# IO_PWR_FMU3_REV_C.net
KiCad netlist of a schematic drawn in Altium Designer
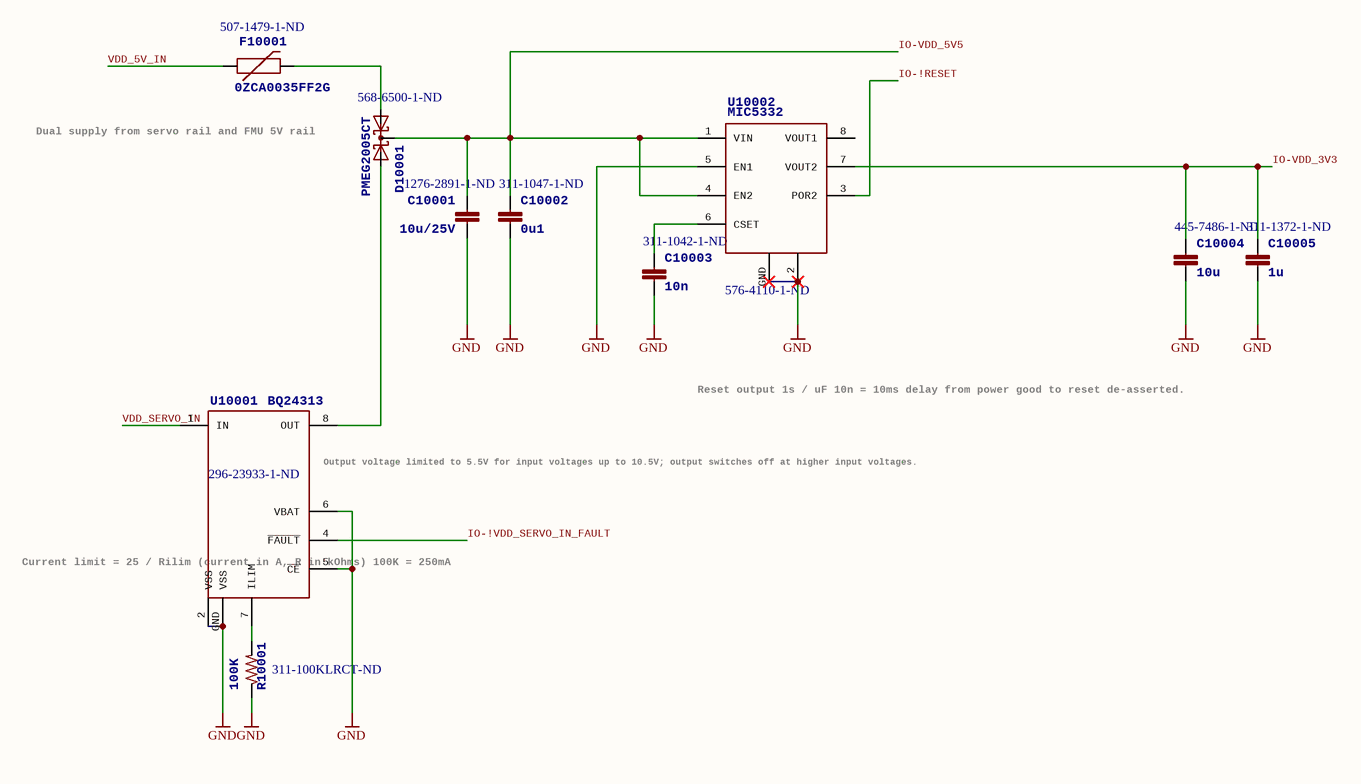
[diagram p0: IO_PWR_FMU3_REV_C.SchDoc]

(export (version "E")
  (design (tool "Eeschema 10.0.6"))
  (components
    (comp (ref "C10001")
      (value "10u/25V")
      (footprint "0805-CAP")
      (description "CAP CER 10UF 25V 10% X5R 0805")
      (fields
        (field (name "PARTNO") "CL21A106KAYNNNE")
        (field (name "SUPPLIER PART NUMBER 1") "1276-2891-1-ND")
        (field (name "3DR_PARTNO") "ECM0714")
      )
      (libsource (lib "pixhawk2") (part "CAP0805"))
    )
    (comp (ref "C10002")
      (value "0u1")
      (footprint "0402-CAP")
      (description "CAP CER 0.1UF 16V Y5V 0402")
      (fields
        (field (name "PARTNO") "CC0402ZRY5V7BB104")
        (field (name "SUPPLIER PART NUMBER 1") "311-1047-1-ND")
        (field (name "3DR_PARTNO") "ECM0700")
      )
      (libsource (lib "pixhawk2") (part "CAP0402"))
    )
    (comp (ref "C10003")
      (value "10n")
      (footprint "0402-CAP")
      (description "CAP CER 10000PF 16V 10% X7R 0402")
      (fields
        (field (name "PARTNO") "CC0402KRX7R7BB103")
        (field (name "SUPPLIER PART NUMBER 1") "311-1042-1-ND")
        (field (name "3DR_PARTNO") "ECM0711")
      )
      (libsource (lib "pixhawk2") (part "CAP0402"))
    )
    (comp (ref "C10004")
      (value "10u")
      (footprint "0603-CAP")
      (description "CAP CER 10UF 10V 10% X5R 0603")
      (fields
        (field (name "PARTNO") "C1608X5R1A106K080AC")
        (field (name "SUPPLIER PART NUMBER 1") "445-7486-1-ND")
        (field (name "3DR_PARTNO") "ECM0712")
      )
      (libsource (lib "pixhawk2") (part "CAP0603"))
    )
    (comp (ref "C10005")
      (value "1u")
      (footprint "0603-CAP")
      (description "CAP CER 1UF 16V Y5V 0603")
      (fields
        (field (name "PARTNO") "CC0603ZRY5V7BB105")
        (field (name "SUPPLIER PART NUMBER 1") "311-1372-1-ND")
        (field (name "3DR_PARTNO") "ECM0705")
      )
      (libsource (lib "pixhawk2") (part "CAP0603"))
    )
    (comp (ref "D10001")
      (value "PMEG2005CT")
      (footprint "SOT23-3")
      (description "DIODE SCHOTTKY 20V 500MA TO236AB")
      (fields (field (name "SUPPLIER PART NUMBER 1") "568-6500-1-ND") (field (name "3DR_PARTNO") "ECM0838"))
      (libsource (lib "pixhawk2") (part "PMEG2005CT"))
    )
    (comp (ref "F10001")
      (value "0ZCA0035FF2G")
      (footprint "PTC-1206")
      (description "PTC RESTTBLE 0.35A 16V CHIP 1206")
      (fields (field (name "SUPPLIER PART NUMBER 1") "507-1479-1-ND") (field (name "3DR_PARTNO") "ECM0802"))
      (libsource (lib "pixhawk2") (part "PTCSMD"))
    )
    (comp (ref "R10001")
      (value "100K")
      (footprint "0402-RES")
      (description "RES 100K OHM 1/16W 1% 0402 SMD")
      (fields
        (field (name "SUPPLIER PART NUMBER 1") "311-100KLRCT-ND")
        (field (name "3DR_PARTNO") "ECM0818")
        (field (name "PARTNO") "RC0402FR-07100KL")
      )
      (libsource (lib "pixhawk2") (part "RESISTOR0402-RES"))
    )
    (comp (ref "U10001")
      (value "BQ24313")
      (footprint "QFN8-DSG")
      (description "IC LI+ CHARGER FRONT END 8-SON")
      (fields
        (field (name "SUPPLIER PART NUMBER 1") "296-23933-1-ND")
        (field (name "3DR_PARTNO") "ECM0824")
        (field (name "PARTNO") "BQ24313DSGT")
      )
      (libsource (lib "pixhawk2") (part "BQ24313"))
    )
    (comp (ref "U10002")
      (value "MIC5332")
      (footprint "MLF-8-EPAD")
      (description "IC REG LDO 3.3V 0.3A 8TMLF")
      (fields
        (field (name "SUPPLIER PART NUMBER 1") "576-4110-1-ND")
        (field (name "3DR_PARTNO") "ECM0832")
        (field (name "PARTNO") "MIC5332-SSYMT TR")
      )
      (libsource (lib "pixhawk2") (part "MIC5332"))
    )
  )
  (nets
    (net (code "1") (name "/IO-!RESET") (class "Default")
      (node (ref "U10002") (pin "3") (pinfunction "POR2_3") (pintype "passive"))
    )
    (net (code "2") (name "/IO-!VDD_SERVO_IN_FAULT") (class "Default")
      (node (ref "U10001") (pin "4") (pinfunction "~{FAULT}_4") (pintype "passive"))
    )
    (net (code "3") (name "/IO-VDD_3V3") (class "Default")
      (node (ref "C10004") (pin "P$1") (pinfunction "1_P$1") (pintype "passive"))
      (node (ref "C10005") (pin "P$1") (pinfunction "1_P$1") (pintype "passive"))
      (node (ref "U10002") (pin "7") (pinfunction "VOUT2_7") (pintype "passive"))
    )
    (net (code "4") (name "/IO-VDD_5V5") (class "Default")
      (node (ref "C10001") (pin "P$1") (pinfunction "1_P$1") (pintype "passive"))
      (node (ref "C10002") (pin "P$1") (pinfunction "1_P$1") (pintype "passive"))
      (node (ref "D10001") (pin "3") (pinfunction "CC_3") (pintype "passive"))
      (node (ref "U10002") (pin "1") (pinfunction "VIN_1") (pintype "passive"))
      (node (ref "U10002") (pin "4") (pinfunction "EN2_4") (pintype "passive"))
    )
    (net (code "5") (name "/VDD_5V_IN") (class "Default")
      (node (ref "F10001") (pin "1") (pinfunction "1_1") (pintype "passive"))
    )
    (net (code "6") (name "/VDD_SERVO_IN") (class "Default")
      (node (ref "U10001") (pin "1") (pinfunction "IN_1") (pintype "passive"))
    )
    (net (code "7") (name "GND") (class "Default")
      (node (ref "C10001") (pin "P$2") (pinfunction "2_P$2") (pintype "passive"))
      (node (ref "C10002") (pin "P$2") (pinfunction "2_P$2") (pintype "passive"))
      (node (ref "C10003") (pin "P$2") (pinfunction "2_P$2") (pintype "passive"))
      (node (ref "C10004") (pin "P$2") (pinfunction "2_P$2") (pintype "passive"))
      (node (ref "C10005") (pin "P$2") (pinfunction "2_P$2") (pintype "passive"))
      (node (ref "R10001") (pin "P$1") (pinfunction "1_P$1") (pintype "passive"))
      (node (ref "U10001") (pin "2") (pinfunction "VSS_2") (pintype "passive"))
      (node (ref "U10001") (pin "5") (pinfunction "~{CE}_5") (pintype "passive"))
      (node (ref "U10001") (pin "6") (pinfunction "VBAT_6") (pintype "passive"))
      (node (ref "U10001") (pin "GND") (pinfunction "VSS_GND") (pintype "passive"))
      (node (ref "U10002") (pin "2") (pinfunction "GND_2") (pintype "power_in"))
      (node (ref "U10002") (pin "5") (pinfunction "EN1_5") (pintype "passive"))
      (node (ref "U10002") (pin "GND") (pinfunction "GND_GND") (pintype "power_in"))
    )
    (net (code "8") (name "Net-(C10003-1)") (class "Default")
      (node (ref "C10003") (pin "P$1") (pinfunction "1_P$1") (pintype "passive"))
      (node (ref "U10002") (pin "6") (pinfunction "CSET_6") (pintype "passive"))
    )
    (net (code "9") (name "Net-(D10001-A1)") (class "Default")
      (node (ref "D10001") (pin "1") (pinfunction "A1_1") (pintype "passive"))
      (node (ref "F10001") (pin "2") (pinfunction "2_2") (pintype "passive"))
    )
    (net (code "10") (name "Net-(D10001-A2)") (class "Default")
      (node (ref "D10001") (pin "2") (pinfunction "A2_2") (pintype "passive"))
      (node (ref "U10001") (pin "8") (pinfunction "OUT_8") (pintype "passive"))
    )
    (net (code "11") (name "Net-(R10001-2)") (class "Default")
      (node (ref "R10001") (pin "P$2") (pinfunction "2_P$2") (pintype "passive"))
      (node (ref "U10001") (pin "7") (pinfunction "ILIM_7") (pintype "passive"))
    )
    (net (code "12") (name "unconnected-(U10002-VOUT1-Pad8)") (class "Default")
      (node (ref "U10002") (pin "8") (pinfunction "VOUT1_8") (pintype "passive"))
    )
  )
)
